# PoE.net
KiCad netlist of a schematic drawn in Altium Designer
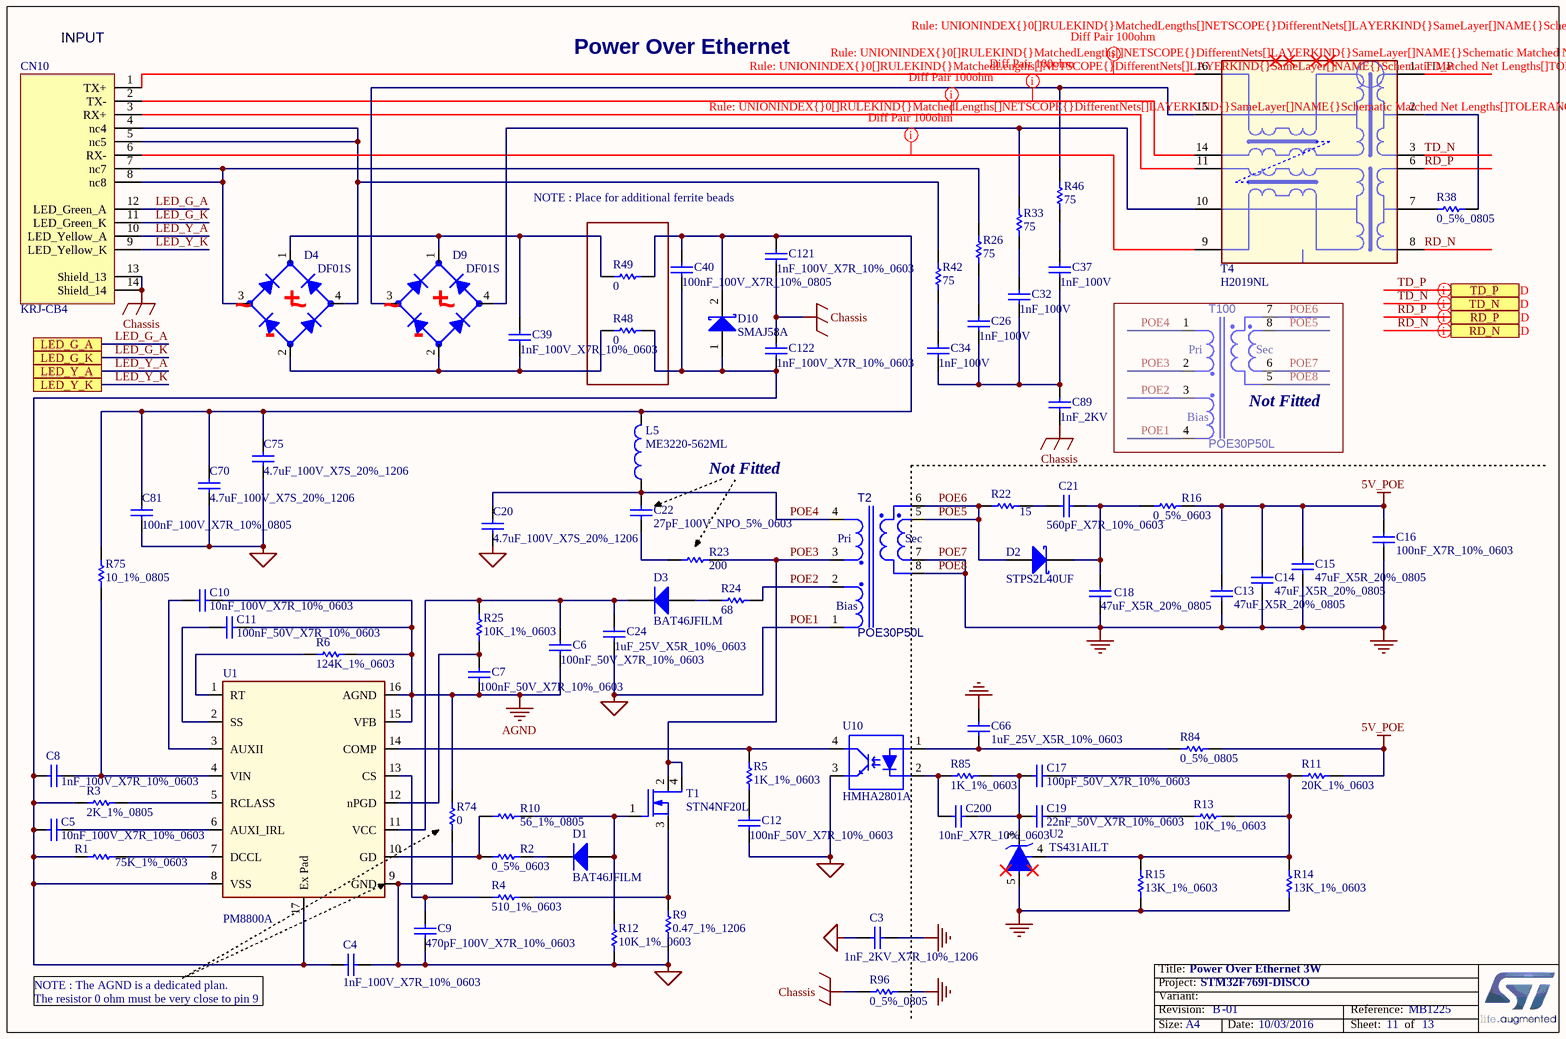
[diagram p0: PoE.SchDoc]

(export (version "E")
  (design (tool "Eeschema 10.0.6"))
  (components
    (comp (ref "C3")
      (value "1nF_2KV_X7R_10%_1206")
      (footprint "1206C")
      (description "Capacitor,1nF,2KV,X7R,10%,1206,YAGEO")
      (libsource (lib "MCD_TOOLS_CAPACITOR") (part "Cap_1nF_2KV_X7R_10%_1206"))
    )
    (comp (ref "C4")
      (value "1nF_100V_X7R_10%_0603")
      (footprint "0603C")
      (description "Capacitor,1nF,100V,X7R,10%,0603,YAGEO")
      (libsource (lib "MCD_TOOLS_CAPACITOR") (part "Cap_1nF_100V_X7R_10%_0603"))
    )
    (comp (ref "C5")
      (value "10nF_100V_X7R_10%_0603")
      (footprint "0603C")
      (description "Capacitor,10nF,100V,X7R,10%,0603,YAGEO")
      (libsource (lib "MCD_TOOLS_CAPACITOR") (part "Cap_10nF_100V_X7R_10%_0603"))
    )
    (comp (ref "C6")
      (value "100nF_50V_X7R_10%_0603")
      (footprint "0603C")
      (description "Capacitor,100nF,50V,X7R,10%,0603,YAGEO")
      (libsource (lib "MCD_TOOLS_CAPACITOR") (part "Cap_100nF_50V_X7R_10%_0603"))
    )
    (comp (ref "C7")
      (value "100nF_50V_X7R_10%_0603")
      (footprint "0603C")
      (description "Capacitor,100nF,50V,X7R,10%,0603,YAGEO")
      (libsource (lib "MCD_TOOLS_CAPACITOR") (part "Cap_100nF_50V_X7R_10%_0603"))
    )
    (comp (ref "C8")
      (value "1nF_100V_X7R_10%_0603")
      (footprint "0603C")
      (description "Capacitor,1nF,100V,X7R,10%,0603,YAGEO")
      (libsource (lib "MCD_TOOLS_CAPACITOR") (part "Cap_1nF_100V_X7R_10%_0603"))
    )
    (comp (ref "C9")
      (value "470pF_100V_X7R_10%_0603")
      (footprint "0603C")
      (description "Capacitor,470pF,100V,X7R,10%,0603,AVX")
      (libsource (lib "MCD_TOOLS_CAPACITOR") (part "Cap_470pF_100V_X7R_10%_0603"))
    )
    (comp (ref "C10")
      (value "10nF_100V_X7R_10%_0603")
      (footprint "0603C")
      (description "Capacitor,10nF,100V,X7R,10%,0603,YAGEO")
      (libsource (lib "MCD_TOOLS_CAPACITOR") (part "Cap_10nF_100V_X7R_10%_0603"))
    )
    (comp (ref "C11")
      (value "100nF_50V_X7R_10%_0603")
      (footprint "0603C")
      (description "Capacitor,100nF,50V,X7R,10%,0603,YAGEO")
      (libsource (lib "MCD_TOOLS_CAPACITOR") (part "Cap_100nF_50V_X7R_10%_0603"))
    )
    (comp (ref "C12")
      (value "100nF_50V_X7R_10%_0603")
      (footprint "0603C")
      (description "Capacitor,100nF,50V,X7R,10%,0603,YAGEO")
      (libsource (lib "MCD_TOOLS_CAPACITOR") (part "Cap_100nF_50V_X7R_10%_0603"))
    )
    (comp (ref "C13")
      (value "47uF_X5R_20%_0805")
      (footprint "0805C")
      (description "Capacitor,47uF,10V,X5R,20%,0805,MURATA")
      (libsource (lib "MCD_TOOLS_CAPACITOR") (part "Cap_47uF_X5R_20%_0805"))
    )
    (comp (ref "C14")
      (value "47uF_X5R_20%_0805")
      (footprint "0805C")
      (description "Capacitor,47uF,10V,X5R,20%,0805,MURATA")
      (libsource (lib "MCD_TOOLS_CAPACITOR") (part "Cap_47uF_X5R_20%_0805"))
    )
    (comp (ref "C15")
      (value "47uF_X5R_20%_0805")
      (footprint "0805C")
      (description "Capacitor,47uF,10V,X5R,20%,0805,MURATA")
      (libsource (lib "MCD_TOOLS_CAPACITOR") (part "Cap_47uF_X5R_20%_0805"))
    )
    (comp (ref "C16")
      (value "100nF_X7R_10%_0603")
      (footprint "0603C")
      (description "Capacitor,100nF,16V,X7R,10%,0603,YAGEO")
      (libsource (lib "MCD_TOOLS_CAPACITOR") (part "Cap_100nF_X7R_10%_0603"))
    )
    (comp (ref "C17")
      (value "100pF_50V_X7R_10%_0603")
      (footprint "0603C")
      (description "Capacitor,100pF,50V,X7R,10%,0603,AVX")
      (libsource (lib "MCD_TOOLS_CAPACITOR") (part "Cap_100pF_50V_X7R_10%_0603"))
    )
    (comp (ref "C18")
      (value "47uF_X5R_20%_0805")
      (footprint "0805C")
      (description "Capacitor,47uF,10V,X5R,20%,0805,MURATA")
      (libsource (lib "MCD_TOOLS_CAPACITOR") (part "Cap_47uF_X5R_20%_0805"))
    )
    (comp (ref "C19")
      (value "22nF_50V_X7R_10%_0603")
      (footprint "0603C")
      (description "Capacitor,22nF,50V,X7R,10%,0603,YAGEO")
      (libsource (lib "MCD_TOOLS_CAPACITOR") (part "Cap_22nF_50V_X7R_10%_0603"))
    )
    (comp (ref "C20")
      (value "4.7uF_100V_X7S_20%_1206")
      (footprint "1206C")
      (description "Capacitor,4.7uF,100V, X7S,20%,1206,AVX")
      (libsource (lib "MCD_TOOLS_CAPACITOR") (part "Cap_4.7uF_100V_X7S_20%_1206"))
    )
    (comp (ref "C21")
      (value "560pF_X7R_10%_0603")
      (footprint "0603C")
      (description "Capacitor,560pF,16V,X7R,10%,0603,AVX")
      (libsource (lib "MCD_TOOLS_CAPACITOR") (part "Cap_560pF_X7R_10%_0603"))
    )
    (comp (ref "C22")
      (value "27pF_100V_NPO_5%_0603")
      (footprint "0603C")
      (description "Capacitor,27pF,100V,NPO,5%,0603,YAGEO")
      (libsource (lib "MCD_TOOLS_CAPACITOR") (part "Cap_27pF_100V_NPO_5%_0603"))
    )
    (comp (ref "C24")
      (value "1uF_25V_X5R_10%_0603")
      (footprint "0603C")
      (description "Capacitor,1uF,25V,X5R,10%,0603,YAGEO")
      (libsource (lib "MCD_TOOLS_CAPACITOR") (part "Cap_1uF_25V_X5R_10%_0603"))
    )
    (comp (ref "C26")
      (value "1nF_100V")
      (footprint "0603C")
      (description "Capacitor,1nF,100V,X7R,10%,0603,YAGEO")
      (libsource (lib "MCD_TOOLS_CAPACITOR") (part "Cap_1nF_100V_X7R_10%_0603"))
    )
    (comp (ref "C32")
      (value "1nF_100V")
      (footprint "0603C")
      (description "Capacitor,1nF,100V,X7R,10%,0603,YAGEO")
      (libsource (lib "MCD_TOOLS_CAPACITOR") (part "Cap_1nF_100V_X7R_10%_0603"))
    )
    (comp (ref "C34")
      (value "1nF_100V")
      (footprint "0603C")
      (description "Capacitor,1nF,100V,X7R,10%,0603,YAGEO")
      (libsource (lib "MCD_TOOLS_CAPACITOR") (part "Cap_1nF_100V_X7R_10%_0603"))
    )
    (comp (ref "C37")
      (value "1nF_100V")
      (footprint "0603C")
      (description "Capacitor,1nF,100V,X7R,10%,0603,YAGEO")
      (libsource (lib "MCD_TOOLS_CAPACITOR") (part "Cap_1nF_100V_X7R_10%_0603"))
    )
    (comp (ref "C39")
      (value "1nF_100V_X7R_10%_0603")
      (footprint "0603C")
      (description "Capacitor,1nF,100V,X7R,10%,0603,YAGEO")
      (libsource (lib "MCD_TOOLS_CAPACITOR") (part "Cap_1nF_100V_X7R_10%_0603"))
    )
    (comp (ref "C40")
      (value "100nF_100V_X7R_10%_0805")
      (footprint "0805C")
      (description "Capacitor,100nF,100V,X7R,10%,0805,TDK")
      (libsource (lib "MCD_TOOLS_CAPACITOR") (part "Cap_100nF_100V_X7R_10%_0805"))
    )
    (comp (ref "C66")
      (value "1uF_25V_X5R_10%_0603")
      (footprint "0603C")
      (description "Capacitor,1uF,25V,X5R,10%,0603,YAGEO")
      (libsource (lib "MCD_TOOLS_CAPACITOR") (part "Cap_1uF_25V_X5R_10%_0603"))
    )
    (comp (ref "C70")
      (value "4.7uF_100V_X7S_20%_1206")
      (footprint "1206C")
      (description "Capacitor,4.7uF,100V, X7S,20%,1206,AVX")
      (libsource (lib "MCD_TOOLS_CAPACITOR") (part "Cap_4.7uF_100V_X7S_20%_1206"))
    )
    (comp (ref "C75")
      (value "4.7uF_100V_X7S_20%_1206")
      (footprint "1206C")
      (description "Capacitor,4.7uF,100V, X7S,20%,1206,AVX")
      (libsource (lib "MCD_TOOLS_CAPACITOR") (part "Cap_4.7uF_100V_X7S_20%_1206"))
    )
    (comp (ref "C81")
      (value "100nF_100V_X7R_10%_0805")
      (footprint "0805C")
      (description "Capacitor,100nF,100V,X7R,10%,0805,TDK")
      (libsource (lib "MCD_TOOLS_CAPACITOR") (part "Cap_100nF_100V_X7R_10%_0805"))
    )
    (comp (ref "C89")
      (value "1nF_2KV")
      (footprint "1206C")
      (description "Capacitor,1nF,2KV,X7R,10%,1206,YAGEO")
      (libsource (lib "MCD_TOOLS_CAPACITOR") (part "Cap_1nF_2KV_X7R_10%_1206"))
    )
    (comp (ref "C121")
      (value "1nF_100V_X7R_10%_0603")
      (footprint "0603C")
      (description "Capacitor,1nF,100V,X7R,10%,0603,YAGEO")
      (libsource (lib "MCD_TOOLS_CAPACITOR") (part "Cap_1nF_100V_X7R_10%_0603"))
    )
    (comp (ref "C122")
      (value "1nF_100V_X7R_10%_0603")
      (footprint "0603C")
      (description "Capacitor,1nF,100V,X7R,10%,0603,YAGEO")
      (libsource (lib "MCD_TOOLS_CAPACITOR") (part "Cap_1nF_100V_X7R_10%_0603"))
    )
    (comp (ref "C200")
      (value "10nF_X7R_10%_0603")
      (footprint "0603C")
      (description "Capacitor,10nF,50V,X7R,10%,0603,YAGEO")
      (libsource (lib "MCD_TOOLS_CAPACITOR") (part "Cap_10nF_X7R_10%_0603"))
    )
    (comp (ref "CN10")
      (value "KRJ-CB4")
      (footprint "RJ45_LED_KRJ-CB4R2GYZNL_EM")
      (description "100 Base-TX (Fast Ethernet)  RJ45 single port (1x1) with LEDS Integrated Connector")
      (libsource (lib "MCD_TOOLS_CONNECTOR") (part "KRJ-CB4"))
    )
    (comp (ref "D1")
      (value "BAT46JFILM")
      (footprint "SOD-323")
      (description "Schottky Single diode(150mA, 100V)")
      (libsource (lib "MCD_TOOLS_MISCELLANEOUS") (part "BAT46JFILM"))
    )
    (comp (ref "D2")
      (value "STPS2L40UF")
      (footprint "SMB")
      (description "Low drop power Schottky rectifier(2A, 40V, 0.34V)")
      (libsource (lib "MCD_TOOLS_MISCELLANEOUS") (part "STPS2L40UF"))
    )
    (comp (ref "D3")
      (value "BAT46JFILM")
      (footprint "SOD-323")
      (description "Schottky Single diode(150mA, 100V)")
      (libsource (lib "MCD_TOOLS_MISCELLANEOUS") (part "BAT46JFILM"))
    )
    (comp (ref "D4")
      (value "DF01S")
      (footprint "DBS101-107G")
      (description "Surface Mount Bridge Rectifiers")
      (libsource (lib "MCD_TOOLS_MISCELLANEOUS") (part "DF01S_SMD"))
    )
    (comp (ref "D9")
      (value "DF01S")
      (footprint "DBS101-107G")
      (description "Surface Mount Bridge Rectifiers")
      (libsource (lib "MCD_TOOLS_MISCELLANEOUS") (part "DF01S_SMD"))
    )
    (comp (ref "D10")
      (value "SMAJ58A")
      (footprint "SMA")
      (description "Transil 400W, VRM=58V")
      (libsource (lib "MCD_TOOLS_MISCELLANEOUS") (part "SMAJ58A"))
    )
    (comp (ref "L5")
      (value "ME3220-562ML")
      (footprint "LSM2_3R2X2R8_H2")
      (description "Power Inductor, 5.6uH, 0.2R, ME3220-562ML, CoilCraft")
      (libsource (lib "MCD_TOOLS_MISCELLANEOUS") (part "ME3220-562ML"))
    )
    (comp (ref "R1")
      (value "75K_1%_0603")
      (footprint "0603R")
      (description "Resistor,75K,0603,1%,YAGEO")
      (libsource (lib "MCD_TOOLS_RESISTOR") (part "Res_75K_1%_0603"))
    )
    (comp (ref "R2")
      (value "0_5%_0603")
      (footprint "0603R-GS")
      (description "Resistor,0,0603,5%,YAGEO")
      (libsource (lib "MCD_TOOLS_RESISTOR") (part "Res_0_5%_0603"))
    )
    (comp (ref "R3")
      (value "2K_1%_0805")
      (footprint "0805R")
      (description "Resistor,2K,0805,1%,YAGEO")
      (libsource (lib "MCD_TOOLS_RESISTOR") (part "Res_2K_1%_0805"))
    )
    (comp (ref "R4")
      (value "510_1%_0603")
      (footprint "0603R")
      (description "Resistor,510,0603,1%,YAGEO")
      (libsource (lib "MCD_TOOLS_RESISTOR") (part "Res_510_1%_0603"))
    )
    (comp (ref "R5")
      (value "1K_1%_0603")
      (footprint "0603R")
      (description "Resistor,1K,0603,1%,YAGEO")
      (libsource (lib "MCD_TOOLS_RESISTOR") (part "Res_1K_1%_0603"))
    )
    (comp (ref "R6")
      (value "124K_1%_0603")
      (footprint "0603R")
      (description "Resistor,124K,0603,1%,YAGEO")
      (libsource (lib "MCD_TOOLS_RESISTOR") (part "Res_124K_1%_0603"))
    )
    (comp (ref "R9")
      (value "0.47_1%_1206")
      (footprint "1206R")
      (description "Resistor,0.47,1206,1%,YAGEO")
      (libsource (lib "MCD_TOOLS_RESISTOR") (part "Res_0.47_1%_1206"))
    )
    (comp (ref "R10")
      (value "56_1%_0805")
      (footprint "0805R")
      (description "Resistor,56,0805,1%,YAGEO")
      (libsource (lib "MCD_TOOLS_RESISTOR") (part "Res_56_1%_0805"))
    )
    (comp (ref "R11")
      (value "20K_1%_0603")
      (footprint "0603R")
      (description "Resistor,20K,0603,1%,YAGEO")
      (libsource (lib "MCD_TOOLS_RESISTOR") (part "Res_20K_1%_0603"))
    )
    (comp (ref "R12")
      (value "10K_1%_0603")
      (footprint "0603R")
      (description "Resistor,10K,0603,1%,YAGEO")
      (libsource (lib "MCD_TOOLS_RESISTOR") (part "Res_10K_1%_0603"))
    )
    (comp (ref "R13")
      (value "10K_1%_0603")
      (footprint "0603R")
      (description "Resistor,10K,0603,1%,YAGEO")
      (libsource (lib "MCD_TOOLS_RESISTOR") (part "Res_10K_1%_0603"))
    )
    (comp (ref "R14")
      (value "13K_1%_0603")
      (footprint "0603R")
      (description "Resistor,13K,0603,1%,YAGEO")
      (libsource (lib "MCD_TOOLS_RESISTOR") (part "Res_13K_1%_0603"))
    )
    (comp (ref "R15")
      (value "13K_1%_0603")
      (footprint "0603R")
      (description "Resistor,13K,0603,1%,YAGEO")
      (libsource (lib "MCD_TOOLS_RESISTOR") (part "Res_13K_1%_0603"))
    )
    (comp (ref "R16")
      (value "0_5%_0603")
      (footprint "0603R-GS")
      (description "Resistor,0,0603,5%,YAGEO")
      (libsource (lib "MCD_TOOLS_RESISTOR") (part "Res_0_5%_0603"))
    )
    (comp (ref "R22")
      (value "15")
      (footprint "0805R")
      (description "Resistor,15,0805,1%,YAGEO")
      (libsource (lib "MCD_TOOLS_RESISTOR") (part "Res_15_1%_0805"))
    )
    (comp (ref "R23")
      (value "200")
      (footprint "1206R")
      (description "Resistor,200,1206,1%,Rohm")
      (libsource (lib "MCD_TOOLS_RESISTOR") (part "Res_200_1%_1206"))
    )
    (comp (ref "R24")
      (value "68")
      (footprint "0805R")
      (description "Resistor,68,0805,1%,YAGEO")
      (libsource (lib "MCD_TOOLS_RESISTOR") (part "Res_68_1%_0805"))
    )
    (comp (ref "R25")
      (value "10K_1%_0603")
      (footprint "0603R")
      (description "Resistor,10K,0603,1%,YAGEO")
      (libsource (lib "MCD_TOOLS_RESISTOR") (part "Res_10K_1%_0603"))
    )
    (comp (ref "R26")
      (value "75")
      (footprint "0805R")
      (description "Resistor,75,0805,1%,YAGEO")
      (libsource (lib "MCD_TOOLS_RESISTOR") (part "Res_75_1%_0805"))
    )
    (comp (ref "R33")
      (value "75")
      (footprint "0805R")
      (description "Resistor,75,0805,1%,YAGEO")
      (libsource (lib "MCD_TOOLS_RESISTOR") (part "Res_75_1%_0805"))
    )
    (comp (ref "R38")
      (value "0_5%_0805")
      (footprint "0805R")
      (description "Resistor,0,0805,5%,YAGEO")
      (libsource (lib "MCD_TOOLS_RESISTOR") (part "Res_0_5%_0805"))
    )
    (comp (ref "R42")
      (value "75")
      (footprint "0805R")
      (description "Resistor,75,0805,1%,YAGEO")
      (libsource (lib "MCD_TOOLS_RESISTOR") (part "Res_75_1%_0805"))
    )
    (comp (ref "R46")
      (value "75")
      (footprint "0805R")
      (description "Resistor,75,0805,1%,YAGEO")
      (libsource (lib "MCD_TOOLS_RESISTOR") (part "Res_75_1%_0805"))
    )
    (comp (ref "R48")
      (value "0")
      (footprint "0805R")
      (description "Resistor,0,0805,5%,YAGEO")
      (libsource (lib "MCD_TOOLS_RESISTOR") (part "Res_0_5%_0805"))
    )
    (comp (ref "R49")
      (value "0")
      (footprint "0805R")
      (description "Resistor,0,0805,5%,YAGEO")
      (libsource (lib "MCD_TOOLS_RESISTOR") (part "Res_0_5%_0805"))
    )
    (comp (ref "R74")
      (value "0")
      (footprint "0603R-GS")
      (description "Resistor,0,0603,5%,YAGEO")
      (libsource (lib "MCD_TOOLS_RESISTOR") (part "Res_0_5%_0603"))
    )
    (comp (ref "R75")
      (value "10_1%_0805")
      (footprint "0805R")
      (description "Resistor,10,0805,1%,Stackpole,1/4W")
      (libsource (lib "MCD_TOOLS_RESISTOR") (part "Res_10_1%_0805"))
    )
    (comp (ref "R84")
      (value "0_5%_0805")
      (footprint "0805R")
      (description "Resistor,0,0805,5%,YAGEO")
      (libsource (lib "MCD_TOOLS_RESISTOR") (part "Res_0_5%_0805"))
    )
    (comp (ref "R85")
      (value "1K_1%_0603")
      (footprint "0603R")
      (description "Resistor,1K,0603,1%,YAGEO")
      (libsource (lib "MCD_TOOLS_RESISTOR") (part "Res_1K_1%_0603"))
    )
    (comp (ref "R96")
      (value "0_5%_0805")
      (footprint "0805R")
      (description "Resistor,0,0805,5%,YAGEO")
      (libsource (lib "MCD_TOOLS_RESISTOR") (part "Res_0_5%_0805"))
    )
    (comp (ref "T1")
      (value "STN4NF20L")
      (footprint "SOT-223")
      (description "N-channel 200 V, 1.1ohm, 1 A, low gate charge STripFET II, Power MOSFET")
      (libsource (lib "MCD_TOOLS_MISCELLANEOUS") (part "STN4NF20L"))
    )
    (comp (ref "T2")
      (value "POE30P50L")
      (footprint "TF_10R9X13R2-12R2X14R4_CPT")
      (description "Flyback Transformers for 3 Watt, PoE applications, CoilCraft Cyntec")
      (fields (field (name "PROVIDED") "Sub Co"))
      (libsource (lib "MCD_TOOLS_MISCELLANEOUS") (part "POE30P_C"))
    )
    (comp (ref "T4")
      (value "H2019NL")
      (footprint "TF_16SM_12R7X9R65")
      (description "10/100BASE-TX VoIP Magnetics Modules, Data Transformer")
      (libsource (lib "MCD_TOOLS_MISCELLANEOUS") (part "H2019"))
    )
    (comp (ref "T100")
      (value "POE30P50L")
      (footprint "TF_8SM_12R04X12R85")
      (description "Flyback Transformers for 3 Watt, PoE applications, Wurth")
      (fields (field (name "PROVIDED") "Sub Co"))
      (libsource (lib "MCD_TOOLS_MISCELLANEOUS") (part "POE30P_W"))
    )
    (comp (ref "U1")
      (value "PM8800A")
      (footprint "TSSOP16_0R65_5x6R4_TP")
      (fields (field (name "PROVIDED") "STM"))
      (libsource (lib "MCD_TOOLS_MISCELLANEOUS") (part "PM8800A"))
    )
    (comp (ref "U2")
      (value "TS431AILT")
      (footprint "SOT23-5")
      (description "Low voltage adjustable shunt reference")
      (libsource (lib "MCD_TOOLS_MISCELLANEOUS") (part "TS431AILT"))
    )
    (comp (ref "U10")
      (value "HMHA2801A")
      (footprint "PC_4SM_1R27_2R5X6R8")
      (description "OPTOISOLATOR 3.7KV TRANSISTOR 4SMD")
      (libsource (lib "MCD_TOOLS_MISCELLANEOUS") (part "HMHA2801A"))
    )
  )
  (nets
    (net (code "1") (name "/LED_G_A") (class "Default")
      (node (ref "CN10") (pin "12") (pinfunction "LED_Green_A_12") (pintype "passive"))
    )
    (net (code "2") (name "/LED_G_K") (class "Default")
      (node (ref "CN10") (pin "11") (pinfunction "LED_Green_K_11") (pintype "passive"))
    )
    (net (code "3") (name "/LED_Y_A") (class "Default")
      (node (ref "CN10") (pin "10") (pinfunction "LED_Yellow_A_10") (pintype "passive"))
    )
    (net (code "4") (name "/LED_Y_K") (class "Default")
      (node (ref "CN10") (pin "9") (pinfunction "LED_Yellow_K_9") (pintype "passive"))
    )
    (net (code "5") (name "/POE2") (class "Default")
      (node (ref "R24") (pin "2") (pinfunction "2_2") (pintype "passive"))
      (node (ref "T100") (pin "3") (pinfunction "3_3") (pintype "passive"))
      (node (ref "T2") (pin "2") (pinfunction "2_2") (pintype "passive"))
    )
    (net (code "6") (name "/POE3") (class "Default")
      (node (ref "R23") (pin "2") (pinfunction "2_2") (pintype "passive"))
      (node (ref "T1") (pin "2") (pinfunction "D_2") (pintype "passive"))
      (node (ref "T1") (pin "4") (pinfunction "D_4") (pintype "passive"))
      (node (ref "T100") (pin "2") (pinfunction "2_2") (pintype "passive"))
      (node (ref "T2") (pin "3") (pinfunction "3_3") (pintype "passive"))
    )
    (net (code "7") (name "/POE4") (class "Default")
      (node (ref "C20") (pin "2") (pinfunction "2_2") (pintype "passive"))
      (node (ref "C22") (pin "2") (pinfunction "2_2") (pintype "passive"))
      (node (ref "L5") (pin "1") (pinfunction "1_1") (pintype "passive"))
      (node (ref "T100") (pin "1") (pinfunction "1_1") (pintype "passive"))
      (node (ref "T2") (pin "4") (pinfunction "4_4") (pintype "passive"))
    )
    (net (code "8") (name "/POE5") (class "Default")
      (node (ref "D2") (pin "1") (pinfunction "A_1") (pintype "passive"))
      (node (ref "R22") (pin "1") (pinfunction "1_1") (pintype "passive"))
      (node (ref "T100") (pin "7") (pinfunction "7_7") (pintype "passive"))
      (node (ref "T100") (pin "8") (pinfunction "8_8") (pintype "passive"))
      (node (ref "T2") (pin "5") (pinfunction "5_5") (pintype "passive"))
      (node (ref "T2") (pin "6") (pinfunction "6_6") (pintype "passive"))
    )
    (net (code "9") (name "/RD_N") (class "Default")
      (node (ref "T4") (pin "8") (pinfunction "rd-_8") (pintype "passive"))
    )
    (net (code "10") (name "/RD_P") (class "Default")
      (node (ref "T4") (pin "6") (pinfunction "rd+_6") (pintype "passive"))
    )
    (net (code "11") (name "/TD_N") (class "Default")
      (node (ref "T4") (pin "3") (pinfunction "td-_3") (pintype "passive"))
    )
    (net (code "12") (name "/TD_P") (class "Default")
      (node (ref "T4") (pin "1") (pinfunction "td+_1") (pintype "passive"))
    )
    (net (code "13") (name "5V_POE") (class "Default")
      (node (ref "C13") (pin "2") (pinfunction "2_2") (pintype "passive"))
      (node (ref "C14") (pin "2") (pinfunction "2_2") (pintype "passive"))
      (node (ref "C15") (pin "2") (pinfunction "2_2") (pintype "passive"))
      (node (ref "C16") (pin "2") (pinfunction "2_2") (pintype "passive"))
      (node (ref "R11") (pin "2") (pinfunction "2_2") (pintype "passive"))
      (node (ref "R16") (pin "2") (pinfunction "2_2") (pintype "passive"))
      (node (ref "R84") (pin "2") (pinfunction "2_2") (pintype "passive"))
    )
    (net (code "14") (name "AGND") (class "Default")
      (node (ref "C10") (pin "2") (pinfunction "2_2") (pintype "passive"))
      (node (ref "C11") (pin "2") (pinfunction "2_2") (pintype "passive"))
      (node (ref "C6") (pin "1") (pinfunction "1_1") (pintype "passive"))
      (node (ref "C7") (pin "1") (pinfunction "1_1") (pintype "passive"))
      (node (ref "R6") (pin "2") (pinfunction "2_2") (pintype "passive"))
      (node (ref "R74") (pin "2") (pinfunction "2_2") (pintype "passive"))
      (node (ref "U1") (pin "15") (pinfunction "VFB_15") (pintype "passive"))
      (node (ref "U1") (pin "16") (pinfunction "AGND_16") (pintype "passive"))
    )
    (net (code "15") (name "Chassis") (class "Default")
      (node (ref "C121") (pin "1") (pinfunction "1_1") (pintype "passive"))
      (node (ref "C122") (pin "2") (pinfunction "2_2") (pintype "passive"))
      (node (ref "C89") (pin "1") (pinfunction "1_1") (pintype "passive"))
      (node (ref "CN10") (pin "13") (pinfunction "Shield_13_13") (pintype "passive"))
      (node (ref "CN10") (pin "14") (pinfunction "Shield_14_14") (pintype "passive"))
      (node (ref "R96") (pin "1") (pinfunction "1_1") (pintype "passive"))
    )
    (net (code "16") (name "GND") (class "Default")
      (node (ref "C13") (pin "1") (pinfunction "1_1") (pintype "passive"))
      (node (ref "C14") (pin "1") (pinfunction "1_1") (pintype "passive"))
      (node (ref "C15") (pin "1") (pinfunction "1_1") (pintype "passive"))
      (node (ref "C16") (pin "1") (pinfunction "1_1") (pintype "passive"))
      (node (ref "C18") (pin "1") (pinfunction "1_1") (pintype "passive"))
      (node (ref "C3") (pin "2") (pinfunction "2_2") (pintype "passive"))
      (node (ref "C66") (pin "2") (pinfunction "2_2") (pintype "passive"))
      (node (ref "R14") (pin "1") (pinfunction "1_1") (pintype "passive"))
      (node (ref "R15") (pin "1") (pinfunction "1_1") (pintype "passive"))
      (node (ref "R96") (pin "2") (pinfunction "2_2") (pintype "passive"))
      (node (ref "T100") (pin "5") (pinfunction "5_5") (pintype "passive"))
      (node (ref "T100") (pin "6") (pinfunction "6_6") (pintype "passive"))
      (node (ref "T2") (pin "7") (pinfunction "7_7") (pintype "passive"))
      (node (ref "T2") (pin "8") (pinfunction "8_8") (pintype "passive"))
      (node (ref "U2") (pin "5") (pinfunction "A_5") (pintype "passive"))
    )
    (net (code "17") (name "GND_POWER_IN") (class "Default")
      (node (ref "C12") (pin "1") (pinfunction "1_1") (pintype "passive"))
      (node (ref "C20") (pin "1") (pinfunction "1_1") (pintype "passive"))
      (node (ref "C24") (pin "1") (pinfunction "1_1") (pintype "passive"))
      (node (ref "C3") (pin "1") (pinfunction "1_1") (pintype "passive"))
      (node (ref "C4") (pin "2") (pinfunction "2_2") (pintype "passive"))
      (node (ref "C70") (pin "1") (pinfunction "1_1") (pintype "passive"))
      (node (ref "C75") (pin "1") (pinfunction "1_1") (pintype "passive"))
      (node (ref "C81") (pin "1") (pinfunction "1_1") (pintype "passive"))
      (node (ref "C9") (pin "1") (pinfunction "1_1") (pintype "passive"))
      (node (ref "R12") (pin "1") (pinfunction "1_1") (pintype "passive"))
      (node (ref "R74") (pin "1") (pinfunction "1_1") (pintype "passive"))
      (node (ref "R9") (pin "1") (pinfunction "1_1") (pintype "passive"))
      (node (ref "T100") (pin "4") (pinfunction "4_4") (pintype "passive"))
      (node (ref "T2") (pin "1") (pinfunction "1_1") (pintype "passive"))
      (node (ref "U1") (pin "9") (pinfunction "GND_9") (pintype "passive"))
      (node (ref "U10") (pin "3") (pinfunction "Emitter_3") (pintype "passive"))
    )
    (net (code "18") (name "Net-(C12-Pad2)") (class "Default")
      (node (ref "C12") (pin "2") (pinfunction "2_2") (pintype "passive"))
      (node (ref "R5") (pin "1") (pinfunction "1_1") (pintype "passive"))
    )
    (net (code "19") (name "Net-(C19-Pad2)") (class "Default")
      (node (ref "C19") (pin "2") (pinfunction "2_2") (pintype "passive"))
      (node (ref "R13") (pin "1") (pinfunction "1_1") (pintype "passive"))
    )
    (net (code "20") (name "Net-(C21-Pad1)") (class "Default")
      (node (ref "C21") (pin "1") (pinfunction "1_1") (pintype "passive"))
      (node (ref "R22") (pin "2") (pinfunction "2_2") (pintype "passive"))
    )
    (net (code "21") (name "Net-(C22-Pad1)") (class "Default")
      (node (ref "C22") (pin "1") (pinfunction "1_1") (pintype "passive"))
      (node (ref "R23") (pin "1") (pinfunction "1_1") (pintype "passive"))
    )
    (net (code "22") (name "Net-(C26-Pad1)") (class "Default")
      (node (ref "C26") (pin "1") (pinfunction "1_1") (pintype "passive"))
      (node (ref "C32") (pin "1") (pinfunction "1_1") (pintype "passive"))
      (node (ref "C34") (pin "1") (pinfunction "1_1") (pintype "passive"))
      (node (ref "C37") (pin "1") (pinfunction "1_1") (pintype "passive"))
      (node (ref "C89") (pin "2") (pinfunction "2_2") (pintype "passive"))
    )
    (net (code "23") (name "Net-(C26-Pad2)") (class "Default")
      (node (ref "C26") (pin "2") (pinfunction "2_2") (pintype "passive"))
      (node (ref "R26") (pin "1") (pinfunction "1_1") (pintype "passive"))
    )
    (net (code "24") (name "Net-(C32-Pad2)") (class "Default")
      (node (ref "C32") (pin "2") (pinfunction "2_2") (pintype "passive"))
      (node (ref "R33") (pin "1") (pinfunction "1_1") (pintype "passive"))
    )
    (net (code "25") (name "Net-(C34-Pad2)") (class "Default")
      (node (ref "C34") (pin "2") (pinfunction "2_2") (pintype "passive"))
      (node (ref "R42") (pin "1") (pinfunction "1_1") (pintype "passive"))
    )
    (net (code "26") (name "Net-(C37-Pad2)") (class "Default")
      (node (ref "C37") (pin "2") (pinfunction "2_2") (pintype "passive"))
      (node (ref "R46") (pin "1") (pinfunction "1_1") (pintype "passive"))
    )
    (net (code "27") (name "Net-(CN10-RX+)") (class "Default")
      (node (ref "CN10") (pin "3") (pinfunction "RX+_3") (pintype "passive"))
      (node (ref "T4") (pin "11") (pinfunction "rx1+_11") (pintype "passive"))
    )
    (net (code "28") (name "Net-(CN10-RX-)") (class "Default")
      (node (ref "CN10") (pin "6") (pinfunction "RX-_6") (pintype "passive"))
      (node (ref "T4") (pin "9") (pinfunction "rx-_9") (pintype "passive"))
    )
    (net (code "29") (name "Net-(CN10-TX+)") (class "Default")
      (node (ref "CN10") (pin "1") (pinfunction "TX+_1") (pintype "passive"))
      (node (ref "T4") (pin "16") (pinfunction "tx1+_16") (pintype "passive"))
    )
    (net (code "30") (name "Net-(CN10-TX-)") (class "Default")
      (node (ref "CN10") (pin "2") (pinfunction "TX-_2") (pintype "passive"))
      (node (ref "T4") (pin "14") (pinfunction "tx1-_14") (pintype "passive"))
    )
    (net (code "31") (name "Net-(CN10-nc4)") (class "Default")
      (node (ref "CN10") (pin "4") (pinfunction "nc4_4") (pintype "passive"))
      (node (ref "CN10") (pin "5") (pinfunction "nc5_5") (pintype "passive"))
      (node (ref "D4") (pin "4") (pinfunction "AC_IN_1_4") (pintype "passive"))
      (node (ref "R42") (pin "2") (pinfunction "2_2") (pintype "passive"))
    )
    (net (code "32") (name "Net-(CN10-nc7)") (class "Default")
      (node (ref "CN10") (pin "7") (pinfunction "nc7_7") (pintype "passive"))
      (node (ref "CN10") (pin "8") (pinfunction "nc8_8") (pintype "passive"))
      (node (ref "D4") (pin "3") (pinfunction "AC_IN_2_3") (pintype "passive"))
      (node (ref "R26") (pin "2") (pinfunction "2_2") (pintype "passive"))
    )
    (net (code "33") (name "Net-(D1-A)") (class "Default")
      (node (ref "D1") (pin "1") (pinfunction "A_1") (pintype "passive"))
      (node (ref "R10") (pin "2") (pinfunction "2_2") (pintype "passive"))
      (node (ref "R12") (pin "2") (pinfunction "2_2") (pintype "passive"))
      (node (ref "T1") (pin "1") (pinfunction "G_1") (pintype "passive"))
    )
    (net (code "34") (name "Net-(D1-K)") (class "Default")
      (node (ref "D1") (pin "2") (pinfunction "K_2") (pintype "passive"))
      (node (ref "R2") (pin "2") (pinfunction "2_2") (pintype "passive"))
    )
    (net (code "35") (name "Net-(D2-K)") (class "Default")
      (node (ref "C18") (pin "2") (pinfunction "2_2") (pintype "passive"))
      (node (ref "C21") (pin "2") (pinfunction "2_2") (pintype "passive"))
      (node (ref "D2") (pin "2") (pinfunction "K_2") (pintype "passive"))
      (node (ref "R16") (pin "1") (pinfunction "1_1") (pintype "passive"))
    )
    (net (code "36") (name "Net-(D3-A)") (class "Default")
      (node (ref "D3") (pin "1") (pinfunction "A_1") (pintype "passive"))
      (node (ref "R24") (pin "1") (pinfunction "1_1") (pintype "passive"))
    )
    (net (code "37") (name "Net-(D3-K)") (class "Default")
      (node (ref "C24") (pin "2") (pinfunction "2_2") (pintype "passive"))
      (node (ref "C6") (pin "2") (pinfunction "2_2") (pintype "passive"))
      (node (ref "D3") (pin "2") (pinfunction "K_2") (pintype "passive"))
      (node (ref "R25") (pin "2") (pinfunction "2_2") (pintype "passive"))
      (node (ref "U1") (pin "11") (pinfunction "VCC_11") (pintype "passive"))
    )
    (net (code "38") (name "Net-(D4-DC_OUT_MINUS)") (class "Default")
      (node (ref "C39") (pin "1") (pinfunction "1_1") (pintype "passive"))
      (node (ref "D4") (pin "2") (pinfunction "DC_OUT_MINUS_2") (pintype "passive"))
      (node (ref "D9") (pin "2") (pinfunction "DC_OUT_MINUS_2") (pintype "passive"))
      (node (ref "R48") (pin "1") (pinfunction "1_1") (pintype "passive"))
    )
    (net (code "39") (name "Net-(D4-DC_OUT_PLUS)") (class "Default")
      (node (ref "C39") (pin "2") (pinfunction "2_2") (pintype "passive"))
      (node (ref "D4") (pin "1") (pinfunction "DC_OUT_PLUS_1") (pintype "passive"))
      (node (ref "D9") (pin "1") (pinfunction "DC_OUT_PLUS_1") (pintype "passive"))
      (node (ref "R49") (pin "1") (pinfunction "1_1") (pintype "passive"))
    )
    (net (code "40") (name "Net-(D9-AC_IN_1)") (class "Default")
      (node (ref "D9") (pin "4") (pinfunction "AC_IN_1_4") (pintype "passive"))
      (node (ref "R33") (pin "2") (pinfunction "2_2") (pintype "passive"))
      (node (ref "T4") (pin "10") (pinfunction "rxct_10") (pintype "passive"))
    )
    (net (code "41") (name "Net-(D9-AC_IN_2)") (class "Default")
      (node (ref "D9") (pin "3") (pinfunction "AC_IN_2_3") (pintype "passive"))
      (node (ref "R46") (pin "2") (pinfunction "2_2") (pintype "passive"))
      (node (ref "T4") (pin "15") (pinfunction "txct_15") (pintype "passive"))
    )
    (net (code "42") (name "Net-(D10-A)") (class "Default")
      (node (ref "C122") (pin "1") (pinfunction "1_1") (pintype "passive"))
      (node (ref "C4") (pin "1") (pinfunction "1_1") (pintype "passive"))
      (node (ref "C40") (pin "1") (pinfunction "1_1") (pintype "passive"))
      (node (ref "C5") (pin "1") (pinfunction "1_1") (pintype "passive"))
      (node (ref "C8") (pin "1") (pinfunction "1_1") (pintype "passive"))
      (node (ref "D10") (pin "1") (pinfunction "A_1") (pintype "passive"))
      (node (ref "R1") (pin "1") (pinfunction "1_1") (pintype "passive"))
      (node (ref "R3") (pin "1") (pinfunction "1_1") (pintype "passive"))
      (node (ref "R48") (pin "2") (pinfunction "2_2") (pintype "passive"))
      (node (ref "U1") (pin "17") (pinfunction "Ex_Pad_17") (pintype "passive"))
      (node (ref "U1") (pin "8") (pinfunction "VSS_8") (pintype "passive"))
    )
    (net (code "43") (name "Net-(D10-K)") (class "Default")
      (node (ref "C121") (pin "2") (pinfunction "2_2") (pintype "passive"))
      (node (ref "C40") (pin "2") (pinfunction "2_2") (pintype "passive"))
      (node (ref "C70") (pin "2") (pinfunction "2_2") (pintype "passive"))
      (node (ref "C75") (pin "2") (pinfunction "2_2") (pintype "passive"))
      (node (ref "C81") (pin "2") (pinfunction "2_2") (pintype "passive"))
      (node (ref "D10") (pin "2") (pinfunction "K_2") (pintype "passive"))
      (node (ref "L5") (pin "2") (pinfunction "2_2") (pintype "passive"))
      (node (ref "R49") (pin "2") (pinfunction "2_2") (pintype "passive"))
      (node (ref "R75") (pin "2") (pinfunction "2_2") (pintype "passive"))
    )
    (net (code "44") (name "Net-(T1-S)") (class "Default")
      (node (ref "R4") (pin "2") (pinfunction "2_2") (pintype "passive"))
      (node (ref "R9") (pin "2") (pinfunction "2_2") (pintype "passive"))
      (node (ref "T1") (pin "3") (pinfunction "S_3") (pintype "passive"))
    )
    (net (code "45") (name "Net-(T4-rct)") (class "Default")
      (node (ref "R38") (pin "1") (pinfunction "1_1") (pintype "passive"))
      (node (ref "T4") (pin "7") (pinfunction "rct_7") (pintype "passive"))
    )
    (net (code "46") (name "Net-(T4-tct)") (class "Default")
      (node (ref "R38") (pin "2") (pinfunction "2_2") (pintype "passive"))
      (node (ref "T4") (pin "2") (pinfunction "tct_2") (pintype "passive"))
    )
    (net (code "47") (name "Net-(U1-AUXII)") (class "Default")
      (node (ref "C10") (pin "1") (pinfunction "1_1") (pintype "passive"))
      (node (ref "U1") (pin "3") (pinfunction "AUXII_3") (pintype "passive"))
    )
    (net (code "48") (name "Net-(U1-AUXI_IRL)") (class "Default")
      (node (ref "C5") (pin "2") (pinfunction "2_2") (pintype "passive"))
      (node (ref "U1") (pin "6") (pinfunction "AUXI_IRL_6") (pintype "passive"))
    )
    (net (code "49") (name "Net-(U1-COMP)") (class "Default")
      (node (ref "R5") (pin "2") (pinfunction "2_2") (pintype "passive"))
      (node (ref "U1") (pin "14") (pinfunction "COMP_14") (pintype "passive"))
      (node (ref "U10") (pin "4") (pinfunction "Collector_4") (pintype "passive"))
    )
    (net (code "50") (name "Net-(U1-CS)") (class "Default")
      (node (ref "C9") (pin "2") (pinfunction "2_2") (pintype "passive"))
      (node (ref "R4") (pin "1") (pinfunction "1_1") (pintype "passive"))
      (node (ref "U1") (pin "13") (pinfunction "CS_13") (pintype "passive"))
    )
    (net (code "51") (name "Net-(U1-DCCL)") (class "Default")
      (node (ref "R1") (pin "2") (pinfunction "2_2") (pintype "passive"))
      (node (ref "U1") (pin "7") (pinfunction "DCCL_7") (pintype "passive"))
    )
    (net (code "52") (name "Net-(U1-GD)") (class "Default")
      (node (ref "R10") (pin "1") (pinfunction "1_1") (pintype "passive"))
      (node (ref "R2") (pin "1") (pinfunction "1_1") (pintype "passive"))
      (node (ref "U1") (pin "10") (pinfunction "GD_10") (pintype "passive"))
    )
    (net (code "53") (name "Net-(U1-RCLASS)") (class "Default")
      (node (ref "R3") (pin "2") (pinfunction "2_2") (pintype "passive"))
      (node (ref "U1") (pin "5") (pinfunction "RCLASS_5") (pintype "passive"))
    )
    (net (code "54") (name "Net-(U1-RT)") (class "Default")
      (node (ref "R6") (pin "1") (pinfunction "1_1") (pintype "passive"))
      (node (ref "U1") (pin "1") (pinfunction "RT_1") (pintype "passive"))
    )
    (net (code "55") (name "Net-(U1-SS)") (class "Default")
      (node (ref "C11") (pin "1") (pinfunction "1_1") (pintype "passive"))
      (node (ref "U1") (pin "2") (pinfunction "SS_2") (pintype "passive"))
    )
    (net (code "56") (name "Net-(U1-VIN)") (class "Default")
      (node (ref "C8") (pin "2") (pinfunction "2_2") (pintype "passive"))
      (node (ref "R75") (pin "1") (pinfunction "1_1") (pintype "passive"))
      (node (ref "U1") (pin "4") (pinfunction "VIN_4") (pintype "passive"))
    )
    (net (code "57") (name "Net-(U1-nPGD)") (class "Default")
      (node (ref "C7") (pin "2") (pinfunction "2_2") (pintype "passive"))
      (node (ref "R25") (pin "1") (pinfunction "1_1") (pintype "passive"))
      (node (ref "U1") (pin "12") (pinfunction "nPGD_12") (pintype "passive"))
    )
    (net (code "58") (name "Net-(U2-K)") (class "Default")
      (node (ref "C17") (pin "1") (pinfunction "1_1") (pintype "passive"))
      (node (ref "C19") (pin "1") (pinfunction "1_1") (pintype "passive"))
      (node (ref "C200") (pin "2") (pinfunction "2_2") (pintype "passive"))
      (node (ref "R85") (pin "2") (pinfunction "2_2") (pintype "passive"))
      (node (ref "U2") (pin "3") (pinfunction "K_3") (pintype "passive"))
    )
    (net (code "59") (name "Net-(U2-REF)") (class "Default")
      (node (ref "C17") (pin "2") (pinfunction "2_2") (pintype "passive"))
      (node (ref "R11") (pin "1") (pinfunction "1_1") (pintype "passive"))
      (node (ref "R13") (pin "2") (pinfunction "2_2") (pintype "passive"))
      (node (ref "R14") (pin "2") (pinfunction "2_2") (pintype "passive"))
      (node (ref "R15") (pin "2") (pinfunction "2_2") (pintype "passive"))
      (node (ref "U2") (pin "4") (pinfunction "REF_4") (pintype "passive"))
    )
    (net (code "60") (name "Net-(U10-Anode)") (class "Default")
      (node (ref "C66") (pin "1") (pinfunction "1_1") (pintype "passive"))
      (node (ref "R84") (pin "1") (pinfunction "1_1") (pintype "passive"))
      (node (ref "U10") (pin "1") (pinfunction "Anode_1") (pintype "passive"))
    )
    (net (code "61") (name "Net-(U10-B)") (class "Default")
      (node (ref "C200") (pin "1") (pinfunction "1_1") (pintype "passive"))
      (node (ref "R85") (pin "1") (pinfunction "1_1") (pintype "passive"))
      (node (ref "U10") (pin "2") (pinfunction "B_2") (pintype "passive"))
    )
    (net (code "62") (name "unconnected-(T4-nc_4-Pad4)") (class "Default")
      (node (ref "T4") (pin "4") (pinfunction "nc_4_4") (pintype "passive+no_connect"))
    )
    (net (code "63") (name "unconnected-(T4-nc_5-Pad5)") (class "Default")
      (node (ref "T4") (pin "5") (pinfunction "nc_5_5") (pintype "passive+no_connect"))
    )
    (net (code "64") (name "unconnected-(T4-nc_12-Pad12)") (class "Default")
      (node (ref "T4") (pin "12") (pinfunction "nc_12_12") (pintype "passive+no_connect"))
    )
    (net (code "65") (name "unconnected-(T4-nc_13-Pad13)") (class "Default")
      (node (ref "T4") (pin "13") (pinfunction "nc_13_13") (pintype "passive+no_connect"))
    )
    (net (code "66") (name "unconnected-(U2-nc_1-Pad1)") (class "Default")
      (node (ref "U2") (pin "1") (pinfunction "nc_1_1") (pintype "passive+no_connect"))
    )
    (net (code "67") (name "unconnected-(U2-nc_2-Pad2)") (class "Default")
      (node (ref "U2") (pin "2") (pinfunction "nc_2_2") (pintype "passive+no_connect"))
    )
  )
)
